# tempsensor.net
KiCad netlist of a schematic drawn in Altium Designer
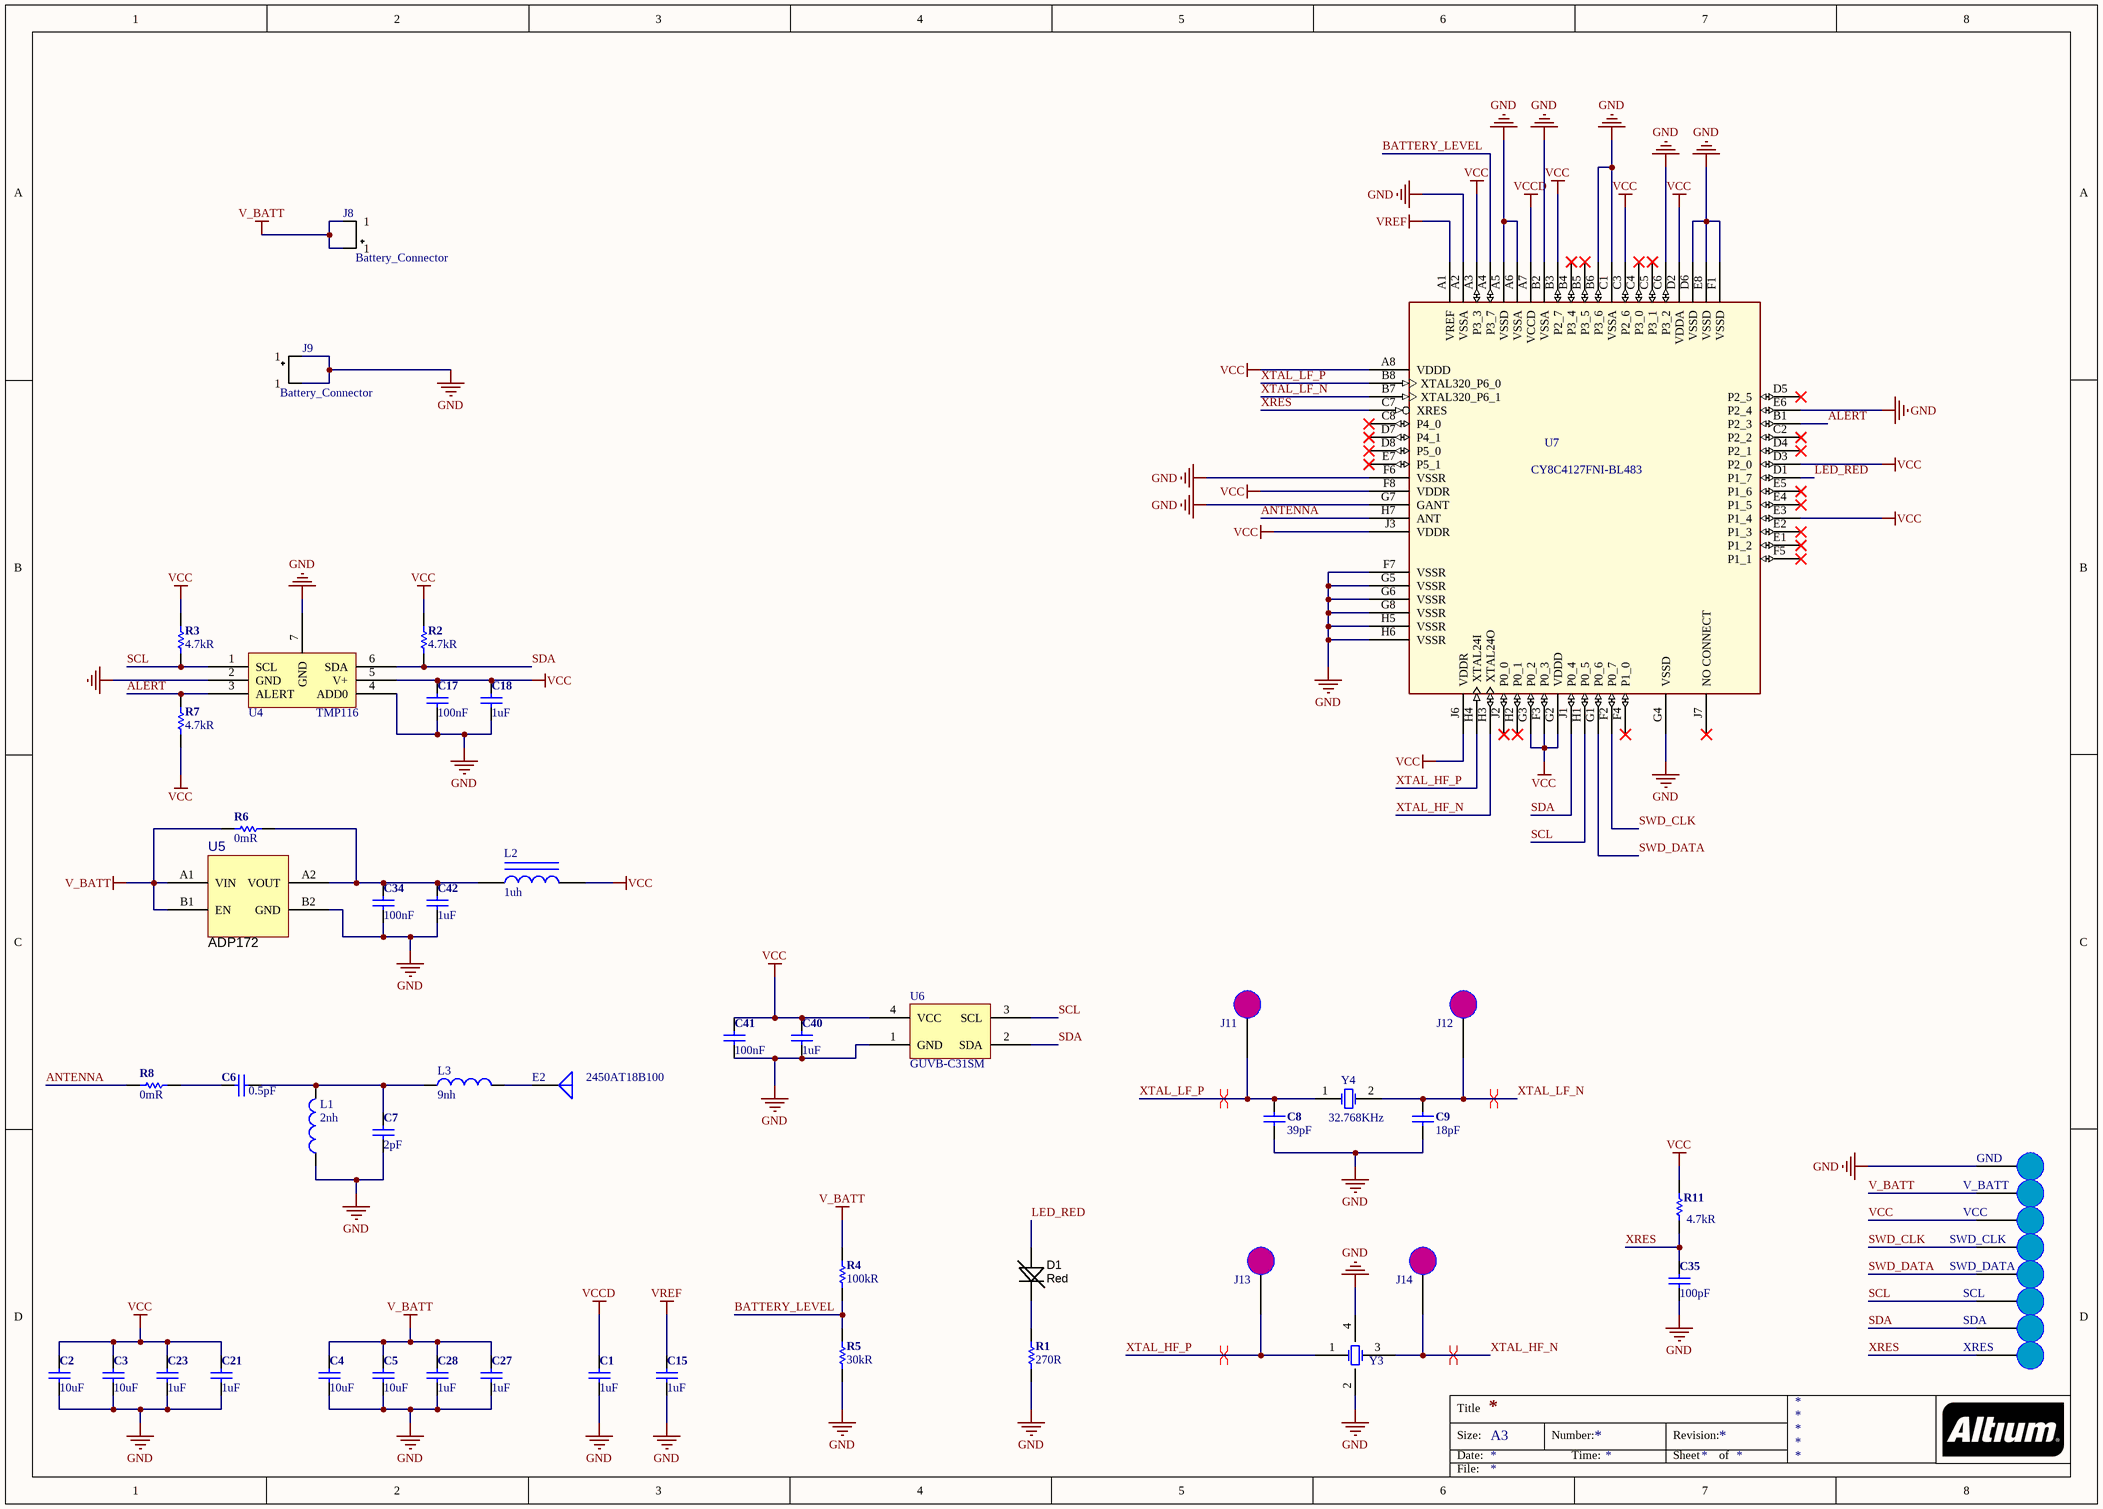
[diagram p0: tempsensor.SchDoc]

(export (version "E")
  (design (tool "Eeschema 10.0.6"))
  (components
    (comp (ref "C1")
      (value "1uF")
      (footprint "CAP_0201(0603)_M")
      (description "___ OHM ___ mW 0201(0603) SMD")
      (fields
        (field (name "MANUFACTURER") "Murata")
        (field (name "MANUFACTURER PART NUMBER") "GRM033C81A105ME05D")
      )
      (libsource (lib "tempsensor") (part "C-0201(0603)"))
    )
    (comp (ref "C2")
      (value "10uF")
      (footprint "CAP_0402(1005)_M")
      (description "___ OHM ___ mW 0402(1005) SMD")
      (fields
        (field (name "MANUFACTURER") "Murata")
        (field (name "MANUFACTURER PART NUMBER") "GRM155R60J106ME15D")
      )
      (libsource (lib "tempsensor") (part "C-0402(1005)"))
    )
    (comp (ref "C3")
      (value "10uF")
      (footprint "CAP_0402(1005)_M")
      (description "___ OHM ___ mW 0402(1005) SMD")
      (fields
        (field (name "MANUFACTURER") "Murata")
        (field (name "MANUFACTURER PART NUMBER") "GRM155R60J106ME15D")
      )
      (libsource (lib "tempsensor") (part "C-0402(1005)"))
    )
    (comp (ref "C4")
      (value "10uF")
      (footprint "CAP_0402(1005)_M")
      (description "___ OHM ___ mW 0402(1005) SMD")
      (fields
        (field (name "MANUFACTURER") "Murata")
        (field (name "MANUFACTURER PART NUMBER") "GRM155R60J106ME15D")
      )
      (libsource (lib "tempsensor") (part "C-0402(1005)"))
    )
    (comp (ref "C5")
      (value "10uF")
      (footprint "CAP_0402(1005)_M")
      (description "___ OHM ___ mW 0402(1005) SMD")
      (fields
        (field (name "MANUFACTURER") "Murata")
        (field (name "MANUFACTURER PART NUMBER") "GRM155R60J106ME15D")
      )
      (libsource (lib "tempsensor") (part "C-0402(1005)"))
    )
    (comp (ref "C6")
      (value "0.5pF")
      (footprint "CAP_0402(1005)_M")
      (description "___ OHM ___ mW 0402(1005) SMD")
      (fields
        (field (name "MANUFACTURER") "Murata")
        (field (name "MANUFACTURER PART NUMBER") "GJM1555C1HR50WB01D")
      )
      (libsource (lib "tempsensor") (part "C-0402(1005)"))
    )
    (comp (ref "C7")
      (value "2pF")
      (footprint "CAP_0402(1005)_M")
      (description "___ OHM ___ mW 0402(1005) SMD")
      (fields
        (field (name "MANUFACTURER") "Murata")
        (field (name "MANUFACTURER PART NUMBER") "GJM1555C1H2R0BB01D")
      )
      (libsource (lib "tempsensor") (part "C-0402(1005)"))
    )
    (comp (ref "C8")
      (value "39pF")
      (footprint "CAP_0402(1005)_M")
      (description "___ OHM ___ mW 0402(1005) SMD")
      (fields
        (field (name "MANUFACTURER") "KEMET")
        (field (name "MANUFACTURER PART NUMBER") "CBR04C390F5GAC")
      )
      (libsource (lib "tempsensor") (part "C-0402(1005)"))
    )
    (comp (ref "C9")
      (value "18pF")
      (footprint "CAP_0402(1005)_M")
      (description "___ OHM ___ mW 0402(1005) SMD")
      (fields
        (field (name "MANUFACTURER") "Murata")
        (field (name "MANUFACTURER PART NUMBER") "GJM1555C1H180FB01D")
      )
      (libsource (lib "tempsensor") (part "C-0402(1005)"))
    )
    (comp (ref "C15")
      (value "1uF")
      (footprint "CAP_0201(0603)_M")
      (description "___ OHM ___ mW 0201(0603) SMD")
      (fields
        (field (name "MANUFACTURER") "Murata")
        (field (name "MANUFACTURER PART NUMBER") "GRM033C81A105ME05D")
      )
      (libsource (lib "tempsensor") (part "C-0201(0603)"))
    )
    (comp (ref "C17")
      (value "100nF")
      (footprint "CAP_0201(0603)_M")
      (description "___ OHM ___ mW 0201(0603) SMD")
      (fields
        (field (name "MANUFACTURER") "Murata")
        (field (name "MANUFACTURER PART NUMBER") "GRM033R61A104ME15D")
      )
      (libsource (lib "tempsensor") (part "C-0201(0603)"))
    )
    (comp (ref "C18")
      (value "1uF")
      (footprint "CAP_0201(0603)_M")
      (description "___ OHM ___ mW 0201(0603) SMD")
      (fields
        (field (name "MANUFACTURER") "Murata")
        (field (name "MANUFACTURER PART NUMBER") "GRM033C81A105ME05D")
      )
      (libsource (lib "tempsensor") (part "C-0201(0603)"))
    )
    (comp (ref "C21")
      (value "1uF")
      (footprint "CAP_0201(0603)_M")
      (description "___ OHM ___ mW 0201(0603) SMD")
      (fields
        (field (name "MANUFACTURER") "Murata")
        (field (name "MANUFACTURER PART NUMBER") "GRM033C81A105ME05D")
      )
      (libsource (lib "tempsensor") (part "C-0201(0603)"))
    )
    (comp (ref "C23")
      (value "1uF")
      (footprint "CAP_0201(0603)_M")
      (description "___ OHM ___ mW 0201(0603) SMD")
      (fields
        (field (name "MANUFACTURER") "Murata")
        (field (name "MANUFACTURER PART NUMBER") "GRM033C81A105ME05D")
      )
      (libsource (lib "tempsensor") (part "C-0201(0603)"))
    )
    (comp (ref "C27")
      (value "1uF")
      (footprint "CAP_0201(0603)_M")
      (description "___ OHM ___ mW 0201(0603) SMD")
      (fields
        (field (name "MANUFACTURER") "Murata")
        (field (name "MANUFACTURER PART NUMBER") "GRM033C81A105ME05D")
      )
      (libsource (lib "tempsensor") (part "C-0201(0603)"))
    )
    (comp (ref "C28")
      (value "1uF")
      (footprint "CAP_0201(0603)_M")
      (description "___ OHM ___ mW 0201(0603) SMD")
      (fields
        (field (name "MANUFACTURER") "Murata")
        (field (name "MANUFACTURER PART NUMBER") "GRM033C81A105ME05D")
      )
      (libsource (lib "tempsensor") (part "C-0201(0603)"))
    )
    (comp (ref "C34")
      (value "100nF")
      (footprint "CAP_0201(0603)_M")
      (description "___ OHM ___ mW 0201(0603) SMD")
      (fields
        (field (name "MANUFACTURER") "Murata")
        (field (name "MANUFACTURER PART NUMBER") "GRM033R61A104ME15D")
      )
      (libsource (lib "tempsensor") (part "C-0201(0603)"))
    )
    (comp (ref "C35")
      (value "100pF")
      (footprint "CAP_0201(0603)_M")
      (description "___ OHM ___ mW 0201(0603) SMD")
      (fields
        (field (name "MANUFACTURER") "Murata")
        (field (name "MANUFACTURER PART NUMBER") "GRM033R71C101KA01D")
      )
      (libsource (lib "tempsensor") (part "C-0201(0603)"))
    )
    (comp (ref "C40")
      (value "1uF")
      (footprint "CAP_0201(0603)_M")
      (description "___ OHM ___ mW 0201(0603) SMD")
      (fields
        (field (name "MANUFACTURER") "Murata")
        (field (name "MANUFACTURER PART NUMBER") "GRM033C81A105ME05D")
      )
      (libsource (lib "tempsensor") (part "C-0201(0603)"))
    )
    (comp (ref "C41")
      (value "100nF")
      (footprint "CAP_0201(0603)_M")
      (description "___ OHM ___ mW 0201(0603) SMD")
      (fields
        (field (name "MANUFACTURER") "Murata")
        (field (name "MANUFACTURER PART NUMBER") "GRM033R61A104ME15D")
      )
      (libsource (lib "tempsensor") (part "C-0201(0603)"))
    )
    (comp (ref "C42")
      (value "1uF")
      (footprint "CAP_0201(0603)_M")
      (description "___ OHM ___ mW 0201(0603) SMD")
      (fields
        (field (name "MANUFACTURER") "Murata")
        (field (name "MANUFACTURER PART NUMBER") "GRM033C81A105ME05D")
      )
      (libsource (lib "tempsensor") (part "C-0201(0603)"))
    )
    (comp (ref "D1")
      (value "Red")
      (footprint "LED_0402(1005)")
      (description "LED, 0402(1005) SMD")
      (fields
        (field (name "MANUFACTURER") "Kingbright")
        (field (name "MANUFACTURER PART NUMBER") "APHHS1005SURCK")
      )
      (libsource (lib "tempsensor") (part "LED_0402(1005)"))
    )
    (comp (ref "E2")
      (value "2450AT18B100")
      (footprint "2450AT18B100")
      (description "2.4 GHz BLE Antenna")
      (fields
        (field (name "MANUFACTURER") "Johanson")
        (field (name "MANUFACTURER PART NUMBER") "2450AT18B100E")
      )
      (libsource (lib "tempsensor") (part "2450AT18B100"))
    )
    (comp (ref "GND")
      (value "Probe-Pin Pad")
      (footprint "Pogo-Pin-Pad")
      (libsource (lib "tempsensor") (part "Probe-Pin Pad"))
    )
    (comp (ref "J8")
      (value "Battery_Connector")
      (footprint "Battery_PAD")
      (libsource (lib "tempsensor") (part "Battery_Connector"))
    )
    (comp (ref "J9")
      (value "Battery_Connector")
      (footprint "Battery_PAD")
      (libsource (lib "tempsensor") (part "Battery_Connector"))
    )
    (comp (ref "J11")
      (value "Probe-CLOCK")
      (footprint "Pogo-CLOCK-PAD")
      (libsource (lib "tempsensor") (part "Probe-CLOCK"))
    )
    (comp (ref "J12")
      (value "Probe-CLOCK")
      (footprint "Pogo-CLOCK-PAD")
      (libsource (lib "tempsensor") (part "Probe-CLOCK"))
    )
    (comp (ref "J13")
      (value "Probe-CLOCK")
      (footprint "Pogo-CLOCK-PAD")
      (libsource (lib "tempsensor") (part "Probe-CLOCK"))
    )
    (comp (ref "J14")
      (value "Probe-CLOCK")
      (footprint "Pogo-CLOCK-PAD")
      (libsource (lib "tempsensor") (part "Probe-CLOCK"))
    )
    (comp (ref "L1")
      (value "2nh")
      (footprint "IND_0402(1005)_M")
      (fields
        (field (name "MANUFACTURER") "Abracon")
        (field (name "MANUFACTURER PART NUMBER") "AISC-0402-2N0J-T")
        (field (name "TOLERANCE") "5%")
      )
      (libsource (lib "tempsensor") (part "I-0402(1005)"))
    )
    (comp (ref "L2")
      (value "1uh")
      (footprint "IND_0402(1005)_M")
      (description "Magnetic-Core Inductor")
      (fields
        (field (name "MANUFACTURER") "TDK")
        (field (name "MANUFACTURER PART NUMBER") "MLZ1005M1R0WT000")
      )
      (libsource (lib "tempsensor") (part "Inductor Iron"))
    )
    (comp (ref "L3")
      (value "9nh")
      (footprint "IND_0402(1005)_M")
      (fields
        (field (name "MANUFACTURER") "Murata")
        (field (name "MANUFACTURER PART NUMBER") "LQW15AN9N0G80D")
        (field (name "TOLERANCE") "2%")
      )
      (libsource (lib "tempsensor") (part "I-0402(1005)"))
    )
    (comp (ref "R1")
      (value "270R")
      (footprint "RES_0201(0603)_M")
      (description "___ OHM ___ mW 0201(0603) SMD")
      (fields
        (field (name "MANUFACTURER") "Yageo")
        (field (name "MANUFACTURER PART NUMBER") "RC0201JR-07270RL")
      )
      (libsource (lib "tempsensor") (part "R-0201(0603)"))
    )
    (comp (ref "R2")
      (value "4.7kR")
      (footprint "RES_0201(0603)_M")
      (description "___ OHM ___ mW 0201(0603) SMD")
      (fields
        (field (name "MANUFACTURER") "Samsung")
        (field (name "MANUFACTURER PART NUMBER") "RC0603F472CS")
      )
      (libsource (lib "tempsensor") (part "R-0201(0603)"))
    )
    (comp (ref "R3")
      (value "4.7kR")
      (footprint "RES_0201(0603)_M")
      (description "___ OHM ___ mW 0201(0603) SMD")
      (fields
        (field (name "MANUFACTURER") "Samsung")
        (field (name "MANUFACTURER PART NUMBER") "RC0603F472CS")
      )
      (libsource (lib "tempsensor") (part "R-0201(0603)"))
    )
    (comp (ref "R4")
      (value "100kR")
      (footprint "RES_0201(0603)_M")
      (description "___ OHM ___ mW 0201(0603) SMD")
      (fields
        (field (name "MANUFACTURER") "Yageo")
        (field (name "MANUFACTURER PART NUMBER") "RC0201FR-07100KL")
      )
      (libsource (lib "tempsensor") (part "R-0201(0603)"))
    )
    (comp (ref "R5")
      (value "30kR")
      (footprint "RES_0201(0603)_M")
      (description "___ OHM ___ mW 0201(0603) SMD")
      (fields
        (field (name "MANUFACTURER") "Yageo")
        (field (name "MANUFACTURER PART NUMBER") "RC0201FR-0730KL")
      )
      (libsource (lib "tempsensor") (part "R-0201(0603)"))
    )
    (comp (ref "R6")
      (value "0mR")
      (footprint "RES_0402(1005)_M")
      (description "___ OHM ___ mW 0402(1005) SMD")
      (fields
        (field (name "MANUFACTURER") "Panasonic")
        (field (name "MANUFACTURER PART NUMBER") "ERJ-2GE0R00X")
      )
      (libsource (lib "tempsensor") (part "R-0402(1005)"))
    )
    (comp (ref "R7")
      (value "4.7kR")
      (footprint "RES_0201(0603)_M")
      (description "___ OHM ___ mW 0201(0603) SMD")
      (fields
        (field (name "MANUFACTURER") "Samsung")
        (field (name "MANUFACTURER PART NUMBER") "RC0603F472CS")
      )
      (libsource (lib "tempsensor") (part "R-0201(0603)"))
    )
    (comp (ref "R8")
      (value "0mR")
      (footprint "RES_0402(1005)_M")
      (description "___ OHM ___ mW 0402(1005) SMD")
      (fields
        (field (name "MANUFACTURER") "Panasonic")
        (field (name "MANUFACTURER PART NUMBER") "ERJ-2GE0R00X")
      )
      (libsource (lib "tempsensor") (part "R-0402(1005)"))
    )
    (comp (ref "R11")
      (value "4.7kR")
      (footprint "RES_0201(0603)_M")
      (description "___ OHM ___ mW 0201(0603) SMD")
      (fields
        (field (name "MANUFACTURER") "Samsung")
        (field (name "MANUFACTURER PART NUMBER") "RC0603F472CS")
      )
      (libsource (lib "tempsensor") (part "R-0201(0603)"))
    )
    (comp (ref "SCL")
      (value "Probe-Pin Pad")
      (footprint "Pogo-Pin-Pad")
      (libsource (lib "tempsensor") (part "Probe-Pin Pad"))
    )
    (comp (ref "SDA")
      (value "Probe-Pin Pad")
      (footprint "Pogo-Pin-Pad")
      (libsource (lib "tempsensor") (part "Probe-Pin Pad"))
    )
    (comp (ref "SWD_CLK")
      (value "Probe-Pin Pad")
      (footprint "Pogo-Pin-Pad")
      (libsource (lib "tempsensor") (part "Probe-Pin Pad"))
    )
    (comp (ref "SWD_DATA")
      (value "Probe-Pin Pad")
      (footprint "Pogo-Pin-Pad")
      (libsource (lib "tempsensor") (part "Probe-Pin Pad"))
    )
    (comp (ref "U4")
      (value "TMP116")
      (footprint "WSON-6")
      (description "TI Digital I2C Temperature Sensor")
      (fields
        (field (name "MANUFACTURER") "Texas Instruments")
        (field (name "MANUFACTURER PART NUMBER") "TMP116AIDRVT")
      )
      (libsource (lib "tempsensor") (part "TMP116"))
    )
    (comp (ref "U5")
      (value "ADP172")
      (footprint "ADP172")
      (description "3V LDO")
      (fields
        (field (name "MANUFACTURER") "Analog Devices")
        (field (name "MANUFACTURER PART NUMBER") "ADP172ACBZ-3.0-R7")
      )
      (libsource (lib "tempsensor") (part "ADP172"))
    )
    (comp (ref "U6")
      (value "GUVB-C31SM")
      (footprint "GUVB-C31SM")
      (libsource (lib "tempsensor") (part "GUVB-C31SM"))
    )
    (comp (ref "U7")
      (value "CY8C4127FNI-BL483")
      (footprint "WLCSP-68")
      (description "PSOC 4 CYBLE")
      (fields
        (field (name "MANUFACTURER") "Cypress")
        (field (name "MANUFACTURER PART NUMBER") "CY8C4247FNI-BL483T")
      )
      (libsource (lib "tempsensor") (part "CY8C4127FNI-BL483"))
    )
    (comp (ref "VCC")
      (value "Probe-Pin Pad")
      (footprint "Pogo-Pin-Pad")
      (libsource (lib "tempsensor") (part "Probe-Pin Pad"))
    )
    (comp (ref "V_BATT")
      (value "Probe-Pin Pad")
      (footprint "Pogo-Pin-Pad")
      (libsource (lib "tempsensor") (part "Probe-Pin Pad"))
    )
    (comp (ref "XRES")
      (value "Probe-Pin Pad")
      (footprint "Pogo-Pin-Pad")
      (libsource (lib "tempsensor") (part "Probe-Pin Pad"))
    )
    (comp (ref "Y3")
      (value "ECX-2236")
      (footprint "ECX-2236")
      (description "24 MHz Crystal")
      (fields
        (field (name "MANUFACTURER") "ECS International")
        (field (name "MANUFACTURER PART NUMBER") "ECS-240-8-36CKM-TR")
      )
      (libsource (lib "tempsensor") (part "ECX-2236"))
    )
    (comp (ref "Y4")
      (value "32.768KHz")
      (footprint "ABS05")
      (description "Crystal Oscillator")
      (fields
        (field (name "MANUFACTURER") "Abracon")
        (field (name "MANUFACTURER PART NUMBER") "ABS05-32.768KHZ-T")
      )
      (libsource (lib "tempsensor") (part "ABS05"))
    )
  )
  (nets
    (net (code "1") (name "/ALERT") (class "Default")
      (node (ref "R7") (pin "1") (pinfunction "1_1") (pintype "passive"))
      (node (ref "U4") (pin "3") (pinfunction "ALERT_3") (pintype "passive"))
      (node (ref "U7") (pin "B1") (pinfunction "P2_3_B1") (pintype "bidirectional"))
    )
    (net (code "2") (name "/ANTENNA") (class "Default")
      (node (ref "R8") (pin "1") (pinfunction "1_1") (pintype "passive"))
      (node (ref "U7") (pin "H7") (pinfunction "ANT_H7") (pintype "passive"))
    )
    (net (code "3") (name "/BATTERY_LEVEL") (class "Default")
      (node (ref "R4") (pin "2") (pinfunction "2_2") (pintype "passive"))
      (node (ref "R5") (pin "1") (pinfunction "1_1") (pintype "passive"))
      (node (ref "U7") (pin "A4") (pinfunction "P3_7_A4") (pintype "bidirectional"))
    )
    (net (code "4") (name "/LED_RED") (class "Default")
      (node (ref "D1") (pin "A") (pinfunction "A_A") (pintype "passive"))
      (node (ref "U7") (pin "D1") (pinfunction "P1_7_D1") (pintype "bidirectional"))
    )
    (net (code "5") (name "/SCL") (class "Default")
      (node (ref "R3") (pin "2") (pinfunction "2_2") (pintype "passive"))
      (node (ref "SCL") (pin "1") (pinfunction "1_1") (pintype "passive"))
      (node (ref "U4") (pin "1") (pinfunction "SCL_1") (pintype "passive"))
      (node (ref "U6") (pin "3") (pinfunction "SCL_3") (pintype "passive"))
      (node (ref "U7") (pin "H1") (pinfunction "P0_5_H1") (pintype "bidirectional"))
    )
    (net (code "6") (name "/SDA") (class "Default")
      (node (ref "R2") (pin "2") (pinfunction "2_2") (pintype "passive"))
      (node (ref "SDA") (pin "1") (pinfunction "1_1") (pintype "passive"))
      (node (ref "U4") (pin "6") (pinfunction "SDA_6") (pintype "passive"))
      (node (ref "U6") (pin "2") (pinfunction "SDA_2") (pintype "passive"))
      (node (ref "U7") (pin "J1") (pinfunction "P0_4_J1") (pintype "bidirectional"))
    )
    (net (code "7") (name "/SWD_CLK") (class "Default")
      (node (ref "SWD_CLK") (pin "1") (pinfunction "1_1") (pintype "passive"))
      (node (ref "U7") (pin "F2") (pinfunction "P0_7_F2") (pintype "bidirectional"))
    )
    (net (code "8") (name "/SWD_DATA") (class "Default")
      (node (ref "SWD_DATA") (pin "1") (pinfunction "1_1") (pintype "passive"))
      (node (ref "U7") (pin "G1") (pinfunction "P0_6_G1") (pintype "bidirectional"))
    )
    (net (code "9") (name "/XRES") (class "Default")
      (node (ref "C35") (pin "1") (pinfunction "1_1") (pintype "passive"))
      (node (ref "R11") (pin "2") (pinfunction "2_2") (pintype "passive"))
      (node (ref "U7") (pin "C7") (pinfunction "XRES_C7") (pintype "input"))
      (node (ref "XRES") (pin "1") (pinfunction "1_1") (pintype "passive"))
    )
    (net (code "10") (name "/XTAL_HF_N") (class "Default")
      (node (ref "J14") (pin "1") (pinfunction "1_1") (pintype "passive"))
      (node (ref "U7") (pin "H3") (pinfunction "XTAL24O_H3") (pintype "bidirectional"))
      (node (ref "Y3") (pin "3") (pinfunction "OSC2_3") (pintype "passive"))
    )
    (net (code "11") (name "/XTAL_HF_P") (class "Default")
      (node (ref "J13") (pin "1") (pinfunction "1_1") (pintype "passive"))
      (node (ref "U7") (pin "H4") (pinfunction "XTAL24I_H4") (pintype "input"))
      (node (ref "Y3") (pin "1") (pinfunction "OSC1_1") (pintype "passive"))
    )
    (net (code "12") (name "/XTAL_LF_N") (class "Default")
      (node (ref "C9") (pin "1") (pinfunction "1_1") (pintype "passive"))
      (node (ref "J12") (pin "1") (pinfunction "1_1") (pintype "passive"))
      (node (ref "U7") (pin "B7") (pinfunction "XTAL320_P6_1_B7") (pintype "input"))
      (node (ref "Y4") (pin "2") (pinfunction "OSC2_2") (pintype "passive"))
    )
    (net (code "13") (name "/XTAL_LF_P") (class "Default")
      (node (ref "C8") (pin "1") (pinfunction "1_1") (pintype "passive"))
      (node (ref "J11") (pin "1") (pinfunction "1_1") (pintype "passive"))
      (node (ref "U7") (pin "B8") (pinfunction "XTAL320_P6_0_B8") (pintype "input"))
      (node (ref "Y4") (pin "1") (pinfunction "OSC1_1") (pintype "passive"))
    )
    (net (code "14") (name "GND") (class "Default")
      (node (ref "C1") (pin "2") (pinfunction "2_2") (pintype "passive"))
      (node (ref "C15") (pin "2") (pinfunction "2_2") (pintype "passive"))
      (node (ref "C17") (pin "2") (pinfunction "2_2") (pintype "passive"))
      (node (ref "C18") (pin "2") (pinfunction "2_2") (pintype "passive"))
      (node (ref "C2") (pin "2") (pinfunction "2_2") (pintype "passive"))
      (node (ref "C21") (pin "2") (pinfunction "2_2") (pintype "passive"))
      (node (ref "C23") (pin "2") (pinfunction "2_2") (pintype "passive"))
      (node (ref "C27") (pin "2") (pinfunction "2_2") (pintype "passive"))
      (node (ref "C28") (pin "2") (pinfunction "2_2") (pintype "passive"))
      (node (ref "C3") (pin "2") (pinfunction "2_2") (pintype "passive"))
      (node (ref "C34") (pin "2") (pinfunction "2_2") (pintype "passive"))
      (node (ref "C35") (pin "2") (pinfunction "2_2") (pintype "passive"))
      (node (ref "C4") (pin "2") (pinfunction "2_2") (pintype "passive"))
      (node (ref "C40") (pin "1") (pinfunction "1_1") (pintype "passive"))
      (node (ref "C41") (pin "1") (pinfunction "1_1") (pintype "passive"))
      (node (ref "C42") (pin "2") (pinfunction "2_2") (pintype "passive"))
      (node (ref "C5") (pin "2") (pinfunction "2_2") (pintype "passive"))
      (node (ref "C7") (pin "2") (pinfunction "2_2") (pintype "passive"))
      (node (ref "C8") (pin "2") (pinfunction "2_2") (pintype "passive"))
      (node (ref "C9") (pin "2") (pinfunction "2_2") (pintype "passive"))
      (node (ref "GND") (pin "1") (pinfunction "1_1") (pintype "passive"))
      (node (ref "J9") (pin "1") (pinfunction "1_1") (pintype "passive"))
      (node (ref "L1") (pin "1") (pinfunction "1_1") (pintype "passive"))
      (node (ref "R1") (pin "2") (pinfunction "2_2") (pintype "passive"))
      (node (ref "R5") (pin "2") (pinfunction "2_2") (pintype "passive"))
      (node (ref "U4") (pin "2") (pinfunction "GND_2") (pintype "passive"))
      (node (ref "U4") (pin "4") (pinfunction "ADD0_4") (pintype "passive"))
      (node (ref "U4") (pin "7") (pinfunction "GND_7") (pintype "passive"))
      (node (ref "U5") (pin "B2") (pinfunction "GND_B2") (pintype "passive"))
      (node (ref "U6") (pin "1") (pinfunction "GND_1") (pintype "passive"))
      (node (ref "U7") (pin "A2") (pinfunction "VSSA_A2") (pintype "power_in"))
      (node (ref "U7") (pin "A5") (pinfunction "VSSD_A5") (pintype "power_in"))
      (node (ref "U7") (pin "A6") (pinfunction "VSSA_A6") (pintype "power_in"))
      (node (ref "U7") (pin "B2") (pinfunction "VSSA_B2") (pintype "power_in"))
      (node (ref "U7") (pin "B6") (pinfunction "P3_6_B6") (pintype "bidirectional"))
      (node (ref "U7") (pin "C1") (pinfunction "VSSA_C1") (pintype "power_in"))
      (node (ref "U7") (pin "C6") (pinfunction "P3_2_C6") (pintype "bidirectional"))
      (node (ref "U7") (pin "D6") (pinfunction "VSSD_D6") (pintype "power_in"))
      (node (ref "U7") (pin "E6") (pinfunction "P2_4_E6") (pintype "bidirectional"))
      (node (ref "U7") (pin "E8") (pinfunction "VSSD_E8") (pintype "power_in"))
      (node (ref "U7") (pin "F1") (pinfunction "VSSD_F1") (pintype "power_in"))
      (node (ref "U7") (pin "F6") (pinfunction "VSSR_F6") (pintype "power_in"))
      (node (ref "U7") (pin "F7") (pinfunction "VSSR_F7") (pintype "power_in"))
      (node (ref "U7") (pin "G4") (pinfunction "VSSD_G4") (pintype "power_in"))
      (node (ref "U7") (pin "G5") (pinfunction "VSSR_G5") (pintype "power_in"))
      (node (ref "U7") (pin "G6") (pinfunction "VSSR_G6") (pintype "power_in"))
      (node (ref "U7") (pin "G7") (pinfunction "GANT_G7") (pintype "power_in"))
      (node (ref "U7") (pin "G8") (pinfunction "VSSR_G8") (pintype "power_in"))
      (node (ref "U7") (pin "H5") (pinfunction "VSSR_H5") (pintype "power_in"))
      (node (ref "U7") (pin "H6") (pinfunction "VSSR_H6") (pintype "power_in"))
      (node (ref "Y3") (pin "2") (pinfunction "GND_2") (pintype "passive"))
      (node (ref "Y3") (pin "4") (pinfunction "GND_4") (pintype "passive"))
    )
    (net (code "15") (name "Net-(C6-Pad1)") (class "Default")
      (node (ref "C6") (pin "1") (pinfunction "1_1") (pintype "passive"))
      (node (ref "R8") (pin "2") (pinfunction "2_2") (pintype "passive"))
    )
    (net (code "16") (name "Net-(C6-Pad2)") (class "Default")
      (node (ref "C6") (pin "2") (pinfunction "2_2") (pintype "passive"))
      (node (ref "C7") (pin "1") (pinfunction "1_1") (pintype "passive"))
      (node (ref "L1") (pin "2") (pinfunction "2_2") (pintype "passive"))
      (node (ref "L3") (pin "1") (pinfunction "1_1") (pintype "passive"))
    )
    (net (code "17") (name "Net-(D1-PadK)") (class "Default")
      (node (ref "D1") (pin "K") (pinfunction "K_K") (pintype "passive"))
      (node (ref "R1") (pin "1") (pinfunction "1_1") (pintype "passive"))
    )
    (net (code "18") (name "Net-(E2-A)") (class "Default")
      (node (ref "E2") (pin "1") (pinfunction "A_1") (pintype "passive"))
      (node (ref "L3") (pin "2") (pinfunction "2_2") (pintype "passive"))
    )
    (net (code "19") (name "Net-(U5-VOUT)") (class "Default")
      (node (ref "C34") (pin "1") (pinfunction "1_1") (pintype "passive"))
      (node (ref "C42") (pin "1") (pinfunction "1_1") (pintype "passive"))
      (node (ref "L2") (pin "1") (pinfunction "1_1") (pintype "passive"))
      (node (ref "R6") (pin "2") (pinfunction "2_2") (pintype "passive"))
      (node (ref "U5") (pin "A2") (pinfunction "VOUT_A2") (pintype "passive"))
    )
    (net (code "20") (name "VCC") (class "Default")
      (node (ref "C17") (pin "1") (pinfunction "1_1") (pintype "passive"))
      (node (ref "C18") (pin "1") (pinfunction "1_1") (pintype "passive"))
      (node (ref "C2") (pin "1") (pinfunction "1_1") (pintype "passive"))
      (node (ref "C21") (pin "1") (pinfunction "1_1") (pintype "passive"))
      (node (ref "C23") (pin "1") (pinfunction "1_1") (pintype "passive"))
      (node (ref "C3") (pin "1") (pinfunction "1_1") (pintype "passive"))
      (node (ref "C40") (pin "2") (pinfunction "2_2") (pintype "passive"))
      (node (ref "C41") (pin "2") (pinfunction "2_2") (pintype "passive"))
      (node (ref "L2") (pin "2") (pinfunction "2_2") (pintype "passive"))
      (node (ref "R11") (pin "1") (pinfunction "1_1") (pintype "passive"))
      (node (ref "R2") (pin "1") (pinfunction "1_1") (pintype "passive"))
      (node (ref "R3") (pin "1") (pinfunction "1_1") (pintype "passive"))
      (node (ref "R7") (pin "2") (pinfunction "2_2") (pintype "passive"))
      (node (ref "U4") (pin "5") (pinfunction "V+_5") (pintype "passive"))
      (node (ref "U6") (pin "4") (pinfunction "VCC_4") (pintype "passive"))
      (node (ref "U7") (pin "A3") (pinfunction "P3_3_A3") (pintype "bidirectional"))
      (node (ref "U7") (pin "A8") (pinfunction "VDDD_A8") (pintype "power_in"))
      (node (ref "U7") (pin "B3") (pinfunction "P2_7_B3") (pintype "bidirectional"))
      (node (ref "U7") (pin "C3") (pinfunction "P2_6_C3") (pintype "bidirectional"))
      (node (ref "U7") (pin "D2") (pinfunction "VDDA_D2") (pintype "power_in"))
      (node (ref "U7") (pin "D3") (pinfunction "P2_0_D3") (pintype "bidirectional"))
      (node (ref "U7") (pin "E3") (pinfunction "P1_4_E3") (pintype "bidirectional"))
      (node (ref "U7") (pin "F3") (pinfunction "P0_3_F3") (pintype "bidirectional"))
      (node (ref "U7") (pin "F8") (pinfunction "VDDR_F8") (pintype "power_in"))
      (node (ref "U7") (pin "G2") (pinfunction "VDDD_G2") (pintype "power_in"))
      (node (ref "U7") (pin "G3") (pinfunction "P0_2_G3") (pintype "bidirectional"))
      (node (ref "U7") (pin "J3") (pinfunction "VDDR_J3") (pintype "power_in"))
      (node (ref "U7") (pin "J6") (pinfunction "VDDR_J6") (pintype "power_in"))
      (node (ref "VCC") (pin "1") (pinfunction "1_1") (pintype "passive"))
    )
    (net (code "21") (name "VCCD") (class "Default")
      (node (ref "C1") (pin "1") (pinfunction "1_1") (pintype "passive"))
      (node (ref "U7") (pin "A7") (pinfunction "VCCD_A7") (pintype "power_in"))
    )
    (net (code "22") (name "VREF") (class "Default")
      (node (ref "C15") (pin "1") (pinfunction "1_1") (pintype "passive"))
      (node (ref "U7") (pin "A1") (pinfunction "VREF_A1") (pintype "power_in"))
    )
    (net (code "23") (name "V_BATT") (class "Default")
      (node (ref "C27") (pin "1") (pinfunction "1_1") (pintype "passive"))
      (node (ref "C28") (pin "1") (pinfunction "1_1") (pintype "passive"))
      (node (ref "C4") (pin "1") (pinfunction "1_1") (pintype "passive"))
      (node (ref "C5") (pin "1") (pinfunction "1_1") (pintype "passive"))
      (node (ref "J8") (pin "1") (pinfunction "1_1") (pintype "passive"))
      (node (ref "R4") (pin "1") (pinfunction "1_1") (pintype "passive"))
      (node (ref "R6") (pin "1") (pinfunction "1_1") (pintype "passive"))
      (node (ref "U5") (pin "A1") (pinfunction "VIN_A1") (pintype "passive"))
      (node (ref "U5") (pin "B1") (pinfunction "EN_B1") (pintype "passive"))
      (node (ref "V_BATT") (pin "1") (pinfunction "1_1") (pintype "passive"))
    )
    (net (code "24") (name "unconnected-(U7-NO_CONNECT-PadJ7)") (class "Default")
      (node (ref "U7") (pin "J7") (pinfunction "NO_CONNECT_J7") (pintype "passive+no_connect"))
    )
    (net (code "25") (name "unconnected-(U7-P0_0-PadJ2)") (class "Default")
      (node (ref "U7") (pin "J2") (pinfunction "P0_0_J2") (pintype "bidirectional+no_connect"))
    )
    (net (code "26") (name "unconnected-(U7-P0_1-PadH2)") (class "Default")
      (node (ref "U7") (pin "H2") (pinfunction "P0_1_H2") (pintype "bidirectional+no_connect"))
    )
    (net (code "27") (name "unconnected-(U7-P1_0-PadF4)") (class "Default")
      (node (ref "U7") (pin "F4") (pinfunction "P1_0_F4") (pintype "bidirectional+no_connect"))
    )
    (net (code "28") (name "unconnected-(U7-P1_1-PadF5)") (class "Default")
      (node (ref "U7") (pin "F5") (pinfunction "P1_1_F5") (pintype "bidirectional+no_connect"))
    )
    (net (code "29") (name "unconnected-(U7-P1_2-PadE1)") (class "Default")
      (node (ref "U7") (pin "E1") (pinfunction "P1_2_E1") (pintype "bidirectional+no_connect"))
    )
    (net (code "30") (name "unconnected-(U7-P1_3-PadE2)") (class "Default")
      (node (ref "U7") (pin "E2") (pinfunction "P1_3_E2") (pintype "bidirectional+no_connect"))
    )
    (net (code "31") (name "unconnected-(U7-P1_5-PadE4)") (class "Default")
      (node (ref "U7") (pin "E4") (pinfunction "P1_5_E4") (pintype "bidirectional+no_connect"))
    )
    (net (code "32") (name "unconnected-(U7-P1_6-PadE5)") (class "Default")
      (node (ref "U7") (pin "E5") (pinfunction "P1_6_E5") (pintype "bidirectional+no_connect"))
    )
    (net (code "33") (name "unconnected-(U7-P2_1-PadD4)") (class "Default")
      (node (ref "U7") (pin "D4") (pinfunction "P2_1_D4") (pintype "bidirectional+no_connect"))
    )
    (net (code "34") (name "unconnected-(U7-P2_2-PadC2)") (class "Default")
      (node (ref "U7") (pin "C2") (pinfunction "P2_2_C2") (pintype "bidirectional+no_connect"))
    )
    (net (code "35") (name "unconnected-(U7-P2_5-PadD5)") (class "Default")
      (node (ref "U7") (pin "D5") (pinfunction "P2_5_D5") (pintype "bidirectional+no_connect"))
    )
    (net (code "36") (name "unconnected-(U7-P3_0-PadC4)") (class "Default")
      (node (ref "U7") (pin "C4") (pinfunction "P3_0_C4") (pintype "bidirectional+no_connect"))
    )
    (net (code "37") (name "unconnected-(U7-P3_1-PadC5)") (class "Default")
      (node (ref "U7") (pin "C5") (pinfunction "P3_1_C5") (pintype "bidirectional+no_connect"))
    )
    (net (code "38") (name "unconnected-(U7-P3_4-PadB4)") (class "Default")
      (node (ref "U7") (pin "B4") (pinfunction "P3_4_B4") (pintype "bidirectional+no_connect"))
    )
    (net (code "39") (name "unconnected-(U7-P3_5-PadB5)") (class "Default")
      (node (ref "U7") (pin "B5") (pinfunction "P3_5_B5") (pintype "bidirectional+no_connect"))
    )
    (net (code "40") (name "unconnected-(U7-P4_0-PadC8)") (class "Default")
      (node (ref "U7") (pin "C8") (pinfunction "P4_0_C8") (pintype "bidirectional+no_connect"))
    )
    (net (code "41") (name "unconnected-(U7-P4_1-PadD7)") (class "Default")
      (node (ref "U7") (pin "D7") (pinfunction "P4_1_D7") (pintype "bidirectional+no_connect"))
    )
    (net (code "42") (name "unconnected-(U7-P5_0-PadD8)") (class "Default")
      (node (ref "U7") (pin "D8") (pinfunction "P5_0_D8") (pintype "bidirectional+no_connect"))
    )
    (net (code "43") (name "unconnected-(U7-P5_1-PadE7)") (class "Default")
      (node (ref "U7") (pin "E7") (pinfunction "P5_1_E7") (pintype "bidirectional+no_connect"))
    )
  )
)
